# GasSensorModule_v2_1.net
KiCad netlist of a schematic drawn in EAGLE
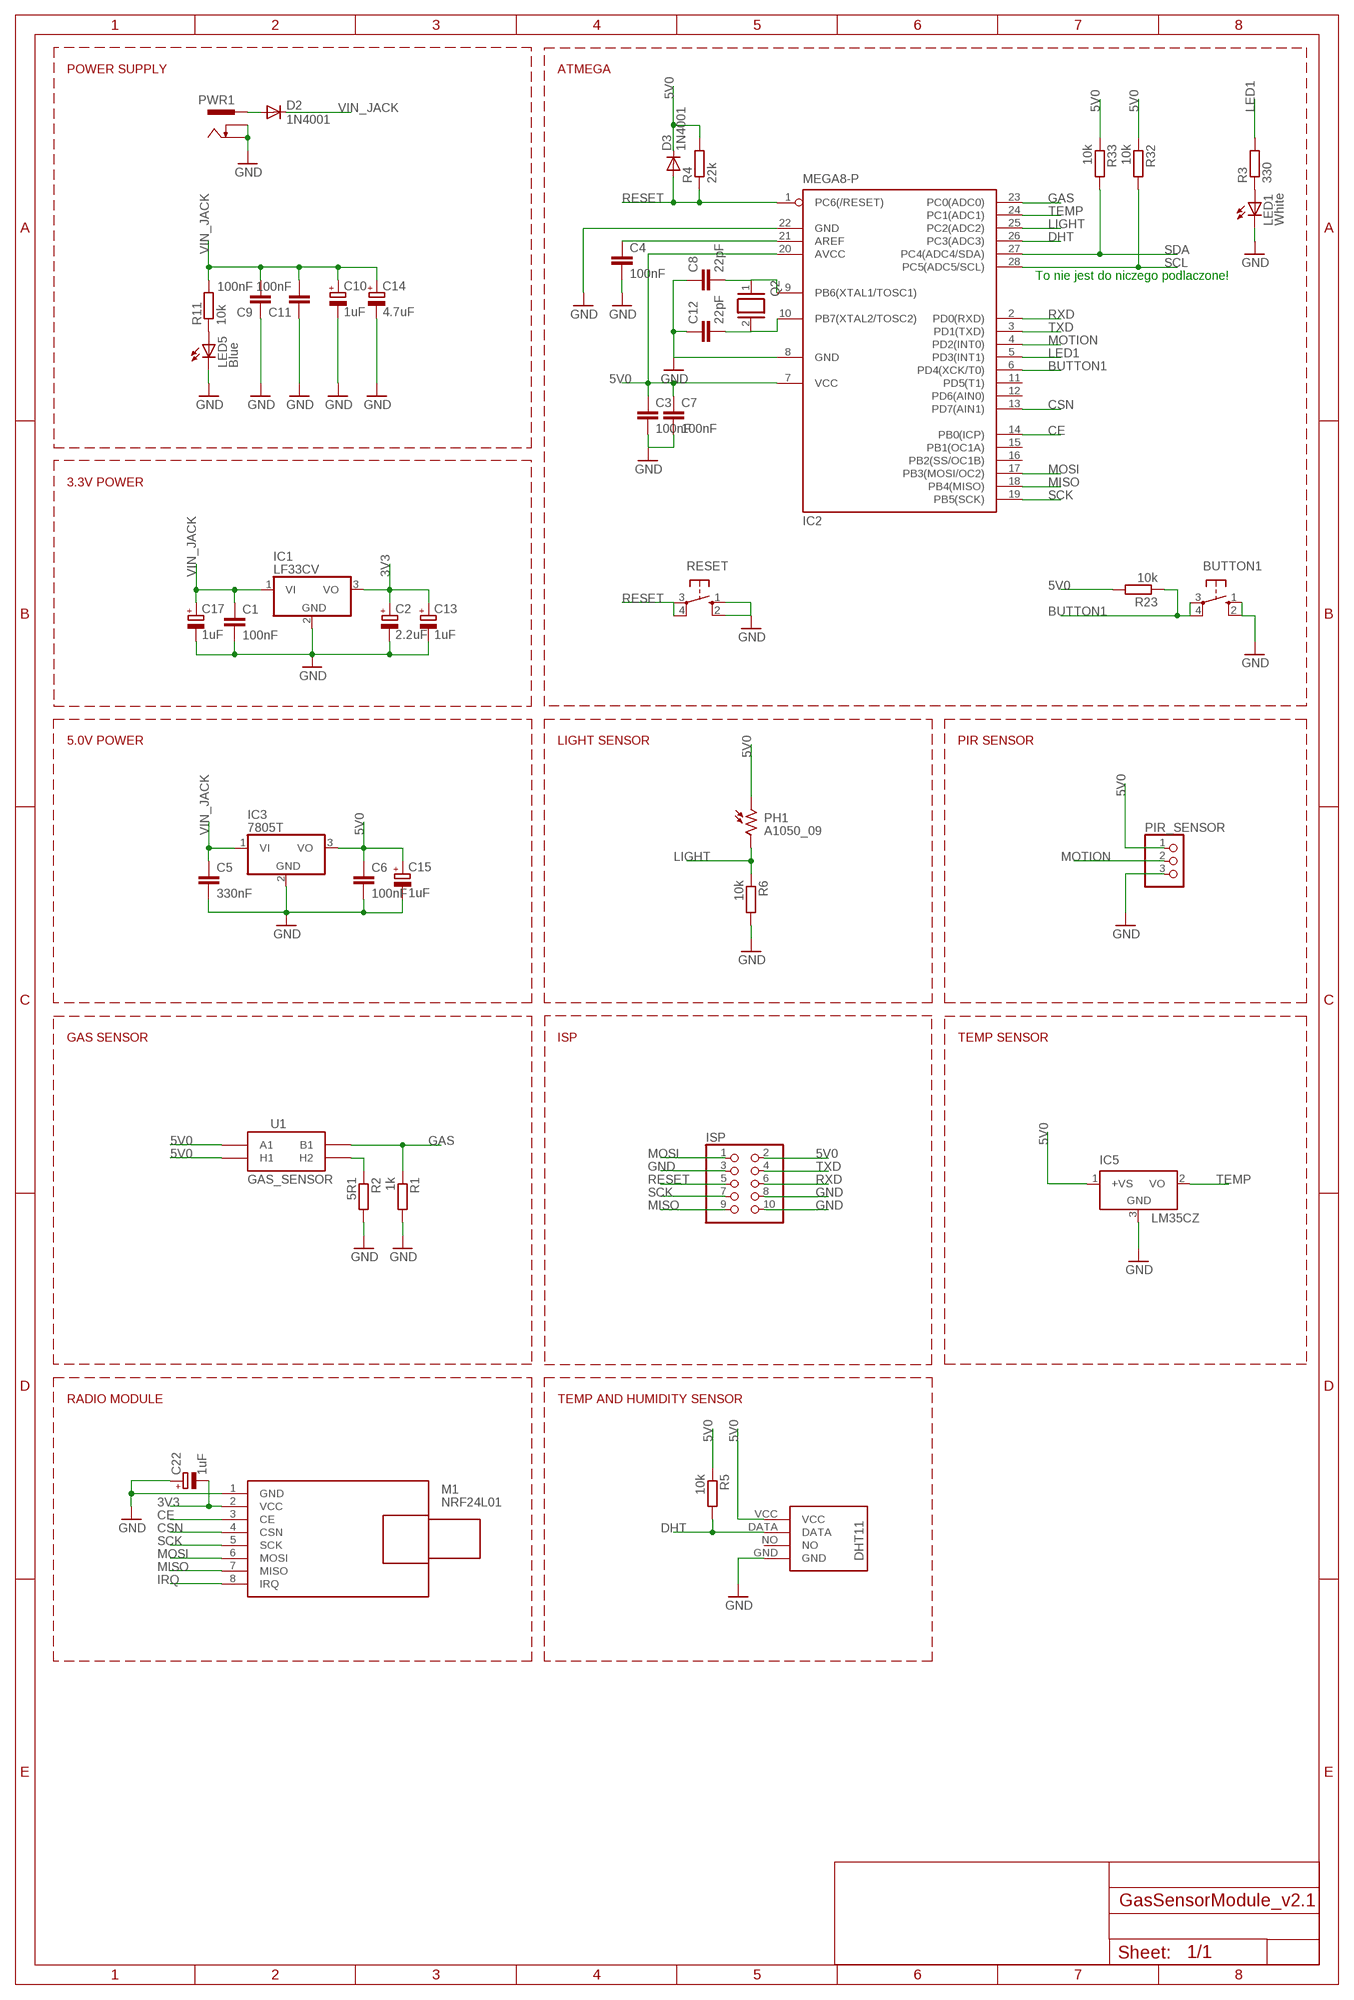
[diagram p0: schematic, sheet 1]

(export (version "E")
  (design (tool "Eeschema 10.0.6"))
  (components
    (comp (ref "BUTTON1")
      (value "10-XX")
      (footprint "eagle-import:B3F-10XX")
      (fields (field (name "MPN") "B3F-1000"))
      (libsource (lib "eagle-import") (part "10-XX"))
    )
    (comp (ref "C1")
      (value "100nF")
      (footprint "eagle-import:C025-025X050")
      (libsource (lib "eagle-import") (part "C-EU025-025X050"))
    )
    (comp (ref "C2")
      (value "2.2uF")
      (footprint "eagle-import:E2,5-5")
      (libsource (lib "eagle-import") (part "CPOL-EUE2.5-5"))
    )
    (comp (ref "C3")
      (value "100nF")
      (footprint "eagle-import:C025-025X050")
      (libsource (lib "eagle-import") (part "C-EU025-025X050"))
    )
    (comp (ref "C4")
      (value "100nF")
      (footprint "eagle-import:C025-025X050")
      (libsource (lib "eagle-import") (part "C-EU025-025X050"))
    )
    (comp (ref "C5")
      (value "330nF")
      (footprint "eagle-import:C025-025X050")
      (libsource (lib "eagle-import") (part "C-EU025-025X050"))
    )
    (comp (ref "C6")
      (value "100nF")
      (footprint "eagle-import:C025-025X050")
      (libsource (lib "eagle-import") (part "C-EU025-025X050"))
    )
    (comp (ref "C7")
      (value "100nF")
      (footprint "eagle-import:C025-025X050")
      (libsource (lib "eagle-import") (part "C-EU025-025X050"))
    )
    (comp (ref "C8")
      (value "22pF")
      (footprint "eagle-import:C025-025X050")
      (libsource (lib "eagle-import") (part "C-EU025-025X050"))
    )
    (comp (ref "C9")
      (value "100nF")
      (footprint "eagle-import:C025-025X050")
      (libsource (lib "eagle-import") (part "C-EU025-025X050"))
    )
    (comp (ref "C10")
      (value "1uF")
      (footprint "eagle-import:E2,5-5")
      (libsource (lib "eagle-import") (part "CPOL-EUE2.5-5"))
    )
    (comp (ref "C11")
      (value "100nF")
      (footprint "eagle-import:C025-025X050")
      (libsource (lib "eagle-import") (part "C-EU025-025X050"))
    )
    (comp (ref "C12")
      (value "22pF")
      (footprint "eagle-import:C025-025X050")
      (libsource (lib "eagle-import") (part "C-EU025-025X050"))
    )
    (comp (ref "C13")
      (value "1uF")
      (footprint "eagle-import:E2,5-5")
      (libsource (lib "eagle-import") (part "CPOL-EUE2.5-5"))
    )
    (comp (ref "C14")
      (value "4.7uF")
      (footprint "eagle-import:E2,5-5")
      (libsource (lib "eagle-import") (part "CPOL-EUE2.5-5"))
    )
    (comp (ref "C15")
      (value "1uF")
      (footprint "eagle-import:E2,5-5")
      (libsource (lib "eagle-import") (part "CPOL-EUE2.5-5"))
    )
    (comp (ref "C17")
      (value "1uF")
      (footprint "eagle-import:E2,5-5")
      (libsource (lib "eagle-import") (part "CPOL-EUE2.5-5"))
    )
    (comp (ref "C22")
      (value "1uF")
      (footprint "eagle-import:E2,5-5")
      (libsource (lib "eagle-import") (part "CPOL-EUE2.5-5"))
    )
    (comp (ref "D2")
      (value "1N4001")
      (footprint "eagle-import:DO41-10")
      (libsource (lib "eagle-import") (part "1N4004"))
    )
    (comp (ref "D3")
      (value "1N4001")
      (footprint "eagle-import:DO41-10")
      (libsource (lib "eagle-import") (part "1N4004"))
    )
    (comp (ref "IC1")
      (value "LF33CV")
      (footprint "eagle-import:TO220H")
      (libsource (lib "eagle-import") (part "78T05"))
    )
    (comp (ref "IC2")
      (value "MEGA8-P")
      (footprint "eagle-import:DIL28-3")
      (libsource (lib "eagle-import") (part "MEGA8-P"))
    )
    (comp (ref "IC3")
      (value "7805T")
      (footprint "eagle-import:TO220H")
      (libsource (lib "eagle-import") (part "78T05"))
    )
    (comp (ref "IC5")
      (value "LM35CZ")
      (footprint "eagle-import:TO92")
      (libsource (lib "eagle-import") (part "LM35CZ"))
    )
    (comp (ref "ISP")
      (value "PINHD-2X5")
      (footprint "eagle-import:2X05")
      (libsource (lib "eagle-import") (part "PINHD-2X5"))
    )
    (comp (ref "LED1")
      (value "White")
      (footprint "eagle-import:LED3MM")
      (libsource (lib "eagle-import") (part "LED3MM"))
    )
    (comp (ref "LED5")
      (value "Blue")
      (footprint "eagle-import:LED3MM")
      (libsource (lib "eagle-import") (part "LED3MM"))
    )
    (comp (ref "M1")
      (value "NRF24L01")
      (footprint "eagle-import:WIRELESS-NRD24L01-PA-EXT")
      (libsource (lib "eagle-import") (part "WIRELESS-NRF24L01-PA-EXT"))
    )
    (comp (ref "PH1")
      (value "A1050_09")
      (footprint "eagle-import:T0-46-A10XX")
      (libsource (lib "eagle-import") (part "A1050_09"))
    )
    (comp (ref "PIR_SENSOR")
      (value "PINHD-1X3")
      (footprint "eagle-import:1X03")
      (libsource (lib "eagle-import") (part "PINHD-1X3"))
    )
    (comp (ref "PWR1")
      (value "PWR-JAKPWR_JACK_UNI_MILLING")
      (footprint "eagle-import:PWR_JACK_UNI_MILLING")
      (libsource (lib "eagle-import") (part "PWR-JAKPWR_JACK_UNI_MILLING"))
    )
    (comp (ref "Q2")
      (value "XTAL/S")
      (footprint "eagle-import:QS")
      (libsource (lib "eagle-import") (part "XTAL/S"))
    )
    (comp (ref "R1")
      (value "1k")
      (footprint "eagle-import:0207_10")
      (libsource (lib "eagle-import") (part "R-EU_0207/10"))
    )
    (comp (ref "R2")
      (value "5R1")
      (footprint "eagle-import:0207_10")
      (libsource (lib "eagle-import") (part "R-EU_0207/10"))
    )
    (comp (ref "R3")
      (value "330")
      (footprint "eagle-import:0207_10")
      (libsource (lib "eagle-import") (part "R-EU_0207/10"))
    )
    (comp (ref "R4")
      (value "22k")
      (footprint "eagle-import:0207_10")
      (libsource (lib "eagle-import") (part "R-EU_0207/10"))
    )
    (comp (ref "R5")
      (value "10k")
      (footprint "eagle-import:0207_10")
      (libsource (lib "eagle-import") (part "R-EU_0207/10"))
    )
    (comp (ref "R6")
      (value "10k")
      (footprint "eagle-import:0207_10")
      (libsource (lib "eagle-import") (part "R-EU_0207/10"))
    )
    (comp (ref "R11")
      (value "10k")
      (footprint "eagle-import:0207_10")
      (libsource (lib "eagle-import") (part "R-EU_0207/10"))
    )
    (comp (ref "R23")
      (value "10k")
      (footprint "eagle-import:0207_10")
      (libsource (lib "eagle-import") (part "R-EU_0207/10"))
    )
    (comp (ref "R32")
      (value "10k")
      (footprint "eagle-import:0207_10")
      (libsource (lib "eagle-import") (part "R-EU_0207/10"))
    )
    (comp (ref "R33")
      (value "10k")
      (footprint "eagle-import:0207_10")
      (libsource (lib "eagle-import") (part "R-EU_0207/10"))
    )
    (comp (ref "RESET")
      (value "10-XX")
      (footprint "eagle-import:B3F-10XX")
      (fields (field (name "MPN") "B3F-1000"))
      (libsource (lib "eagle-import") (part "10-XX"))
    )
    (comp (ref "U$1")
      (value "DHT11-PION.")
      (footprint "eagle-import:DHT11-PION.")
      (libsource (lib "eagle-import") (part "DHT11-PION."))
    )
    (comp (ref "U1")
      (value "GAS_SENSOR")
      (footprint "eagle-import:MQ-3")
      (libsource (lib "eagle-import") (part "GAS_SENSOR"))
    )
  )
  (nets
    (net (code "1") (name "/3V3") (class "Default")
      (node (ref "C13") (pin "+") (pinfunction "+_+") (pintype "passive"))
      (node (ref "C2") (pin "+") (pinfunction "+_+") (pintype "passive"))
      (node (ref "C22") (pin "-") (pinfunction "-_-") (pintype "passive"))
      (node (ref "IC1") (pin "3") (pinfunction "VO_3") (pintype "passive"))
      (node (ref "M1") (pin "2") (pinfunction "VCC_2") (pintype "power_in"))
    )
    (net (code "2") (name "/5V0") (class "Default")
      (node (ref "C15") (pin "+") (pinfunction "+_+") (pintype "passive"))
      (node (ref "C3") (pin "1") (pinfunction "1_1") (pintype "passive"))
      (node (ref "C6") (pin "1") (pinfunction "1_1") (pintype "passive"))
      (node (ref "C7") (pin "1") (pinfunction "1_1") (pintype "passive"))
      (node (ref "D3") (pin "C") (pinfunction "C_C") (pintype "passive"))
      (node (ref "IC2") (pin "20") (pinfunction "AVCC_20") (pintype "power_in"))
      (node (ref "IC2") (pin "7") (pinfunction "VCC_7") (pintype "power_in"))
      (node (ref "IC3") (pin "3") (pinfunction "VO_3") (pintype "passive"))
      (node (ref "IC5") (pin "1") (pinfunction "+VS_1") (pintype "input"))
      (node (ref "ISP") (pin "2") (pinfunction "2_2") (pintype "passive"))
      (node (ref "PH1") (pin "1") (pinfunction "1_1") (pintype "passive"))
      (node (ref "PIR_SENSOR") (pin "1") (pinfunction "1_1") (pintype "passive"))
      (node (ref "R23") (pin "2") (pinfunction "2_2") (pintype "passive"))
      (node (ref "R32") (pin "1") (pinfunction "1_1") (pintype "passive"))
      (node (ref "R33") (pin "1") (pinfunction "1_1") (pintype "passive"))
      (node (ref "R4") (pin "2") (pinfunction "2_2") (pintype "passive"))
      (node (ref "R5") (pin "1") (pinfunction "1_1") (pintype "passive"))
      (node (ref "U$1") (pin "VCC") (pinfunction "VCC_VCC") (pintype "bidirectional"))
      (node (ref "U1") (pin "A1") (pinfunction "A1_A1") (pintype "bidirectional"))
      (node (ref "U1") (pin "HA") (pinfunction "H1_HA") (pintype "bidirectional"))
    )
    (net (code "3") (name "/BUTTON1") (class "Default")
      (node (ref "BUTTON1") (pin "3") (pinfunction "P_3") (pintype "passive"))
      (node (ref "BUTTON1") (pin "4") (pinfunction "P1_4") (pintype "passive"))
      (node (ref "IC2") (pin "6") (pinfunction "PD4(XCK/T0)_6") (pintype "bidirectional"))
      (node (ref "R23") (pin "1") (pinfunction "1_1") (pintype "passive"))
    )
    (net (code "4") (name "/CE") (class "Default")
      (node (ref "IC2") (pin "14") (pinfunction "PB0(ICP)_14") (pintype "bidirectional"))
      (node (ref "M1") (pin "3") (pinfunction "CE_3") (pintype "bidirectional"))
    )
    (net (code "5") (name "/CSN") (class "Default")
      (node (ref "IC2") (pin "13") (pinfunction "PD7(AIN1)_13") (pintype "bidirectional"))
      (node (ref "M1") (pin "4") (pinfunction "CSN_4") (pintype "bidirectional"))
    )
    (net (code "6") (name "/DHT") (class "Default")
      (node (ref "IC2") (pin "26") (pinfunction "PC3(ADC3)_26") (pintype "bidirectional"))
      (node (ref "R5") (pin "2") (pinfunction "2_2") (pintype "passive"))
      (node (ref "U$1") (pin "DATA") (pinfunction "DATA_DATA") (pintype "bidirectional"))
    )
    (net (code "7") (name "/GAS") (class "Default")
      (node (ref "IC2") (pin "23") (pinfunction "PC0(ADC0)_23") (pintype "bidirectional"))
      (node (ref "R1") (pin "1") (pinfunction "1_1") (pintype "passive"))
      (node (ref "U1") (pin "B1") (pinfunction "B1_B1") (pintype "bidirectional"))
    )
    (net (code "8") (name "/IRQ") (class "Default")
      (node (ref "M1") (pin "8") (pinfunction "IRQ_8") (pintype "bidirectional"))
    )
    (net (code "9") (name "/LED1") (class "Default")
      (node (ref "IC2") (pin "5") (pinfunction "PD3(INT1)_5") (pintype "bidirectional"))
      (node (ref "R3") (pin "2") (pinfunction "2_2") (pintype "passive"))
    )
    (net (code "10") (name "/LIGHT") (class "Default")
      (node (ref "IC2") (pin "25") (pinfunction "PC2(ADC2)_25") (pintype "bidirectional"))
      (node (ref "PH1") (pin "2") (pinfunction "2_2") (pintype "passive"))
      (node (ref "R6") (pin "1") (pinfunction "1_1") (pintype "passive"))
    )
    (net (code "11") (name "/MISO") (class "Default")
      (node (ref "IC2") (pin "18") (pinfunction "PB4(MISO)_18") (pintype "bidirectional"))
      (node (ref "ISP") (pin "9") (pinfunction "9_9") (pintype "passive"))
      (node (ref "M1") (pin "7") (pinfunction "MISO_7") (pintype "bidirectional"))
    )
    (net (code "12") (name "/MOSI") (class "Default")
      (node (ref "IC2") (pin "17") (pinfunction "PB3(MOSI/OC2)_17") (pintype "bidirectional"))
      (node (ref "ISP") (pin "1") (pinfunction "1_1") (pintype "passive"))
      (node (ref "M1") (pin "6") (pinfunction "MOSI_6") (pintype "bidirectional"))
    )
    (net (code "13") (name "/MOTION") (class "Default")
      (node (ref "IC2") (pin "4") (pinfunction "PD2(INT0)_4") (pintype "bidirectional"))
      (node (ref "PIR_SENSOR") (pin "2") (pinfunction "2_2") (pintype "passive"))
    )
    (net (code "14") (name "/RESET") (class "Default")
      (node (ref "D3") (pin "A") (pinfunction "A_A") (pintype "passive"))
      (node (ref "IC2") (pin "1") (pinfunction "PC6(/RESET)_1") (pintype "bidirectional"))
      (node (ref "ISP") (pin "5") (pinfunction "5_5") (pintype "passive"))
      (node (ref "R4") (pin "1") (pinfunction "1_1") (pintype "passive"))
      (node (ref "RESET") (pin "3") (pinfunction "P_3") (pintype "passive"))
      (node (ref "RESET") (pin "4") (pinfunction "P1_4") (pintype "passive"))
    )
    (net (code "15") (name "/RXD") (class "Default")
      (node (ref "IC2") (pin "2") (pinfunction "PD0(RXD)_2") (pintype "bidirectional"))
      (node (ref "ISP") (pin "6") (pinfunction "6_6") (pintype "passive"))
    )
    (net (code "16") (name "/SCK") (class "Default")
      (node (ref "IC2") (pin "19") (pinfunction "PB5(SCK)_19") (pintype "bidirectional"))
      (node (ref "ISP") (pin "7") (pinfunction "7_7") (pintype "passive"))
      (node (ref "M1") (pin "5") (pinfunction "SCK_5") (pintype "bidirectional"))
    )
    (net (code "17") (name "/SCL") (class "Default")
      (node (ref "IC2") (pin "28") (pinfunction "PC5(ADC5/SCL)_28") (pintype "bidirectional"))
      (node (ref "R32") (pin "2") (pinfunction "2_2") (pintype "passive"))
    )
    (net (code "18") (name "/SDA") (class "Default")
      (node (ref "IC2") (pin "27") (pinfunction "PC4(ADC4/SDA)_27") (pintype "bidirectional"))
      (node (ref "R33") (pin "2") (pinfunction "2_2") (pintype "passive"))
    )
    (net (code "19") (name "/TEMP") (class "Default")
      (node (ref "IC2") (pin "24") (pinfunction "PC1(ADC1)_24") (pintype "bidirectional"))
      (node (ref "IC5") (pin "2") (pinfunction "VO_2") (pintype "input"))
    )
    (net (code "20") (name "/TXD") (class "Default")
      (node (ref "IC2") (pin "3") (pinfunction "PD1(TXD)_3") (pintype "bidirectional"))
      (node (ref "ISP") (pin "4") (pinfunction "4_4") (pintype "passive"))
    )
    (net (code "21") (name "/VIN_JACK") (class "Default")
      (node (ref "C1") (pin "1") (pinfunction "1_1") (pintype "passive"))
      (node (ref "C10") (pin "+") (pinfunction "+_+") (pintype "passive"))
      (node (ref "C11") (pin "2") (pinfunction "2_2") (pintype "passive"))
      (node (ref "C14") (pin "+") (pinfunction "+_+") (pintype "passive"))
      (node (ref "C17") (pin "+") (pinfunction "+_+") (pintype "passive"))
      (node (ref "C5") (pin "1") (pinfunction "1_1") (pintype "passive"))
      (node (ref "C9") (pin "2") (pinfunction "2_2") (pintype "passive"))
      (node (ref "D2") (pin "C") (pinfunction "C_C") (pintype "passive"))
      (node (ref "IC1") (pin "1") (pinfunction "VI_1") (pintype "input"))
      (node (ref "IC3") (pin "1") (pinfunction "VI_1") (pintype "input"))
      (node (ref "R11") (pin "2") (pinfunction "2_2") (pintype "passive"))
    )
    (net (code "22") (name "GND") (class "Default")
      (node (ref "BUTTON1") (pin "1") (pinfunction "S_1") (pintype "passive"))
      (node (ref "BUTTON1") (pin "2") (pinfunction "S1_2") (pintype "passive"))
      (node (ref "C1") (pin "2") (pinfunction "2_2") (pintype "passive"))
      (node (ref "C10") (pin "-") (pinfunction "-_-") (pintype "passive"))
      (node (ref "C11") (pin "1") (pinfunction "1_1") (pintype "passive"))
      (node (ref "C12") (pin "1") (pinfunction "1_1") (pintype "passive"))
      (node (ref "C13") (pin "-") (pinfunction "-_-") (pintype "passive"))
      (node (ref "C14") (pin "-") (pinfunction "-_-") (pintype "passive"))
      (node (ref "C15") (pin "-") (pinfunction "-_-") (pintype "passive"))
      (node (ref "C17") (pin "-") (pinfunction "-_-") (pintype "passive"))
      (node (ref "C2") (pin "-") (pinfunction "-_-") (pintype "passive"))
      (node (ref "C22") (pin "+") (pinfunction "+_+") (pintype "passive"))
      (node (ref "C3") (pin "2") (pinfunction "2_2") (pintype "passive"))
      (node (ref "C4") (pin "2") (pinfunction "2_2") (pintype "passive"))
      (node (ref "C5") (pin "2") (pinfunction "2_2") (pintype "passive"))
      (node (ref "C6") (pin "2") (pinfunction "2_2") (pintype "passive"))
      (node (ref "C7") (pin "2") (pinfunction "2_2") (pintype "passive"))
      (node (ref "C8") (pin "1") (pinfunction "1_1") (pintype "passive"))
      (node (ref "C9") (pin "1") (pinfunction "1_1") (pintype "passive"))
      (node (ref "IC1") (pin "2") (pinfunction "GND_2") (pintype "passive"))
      (node (ref "IC2") (pin "22") (pinfunction "GND_22") (pintype "power_in"))
      (node (ref "IC2") (pin "8") (pinfunction "GND_8") (pintype "power_in"))
      (node (ref "IC3") (pin "2") (pinfunction "GND_2") (pintype "passive"))
      (node (ref "IC5") (pin "3") (pinfunction "GND_3") (pintype "power_in"))
      (node (ref "ISP") (pin "10") (pinfunction "10_10") (pintype "passive"))
      (node (ref "ISP") (pin "3") (pinfunction "3_3") (pintype "passive"))
      (node (ref "ISP") (pin "8") (pinfunction "8_8") (pintype "passive"))
      (node (ref "LED1") (pin "K") (pinfunction "C_K") (pintype "passive"))
      (node (ref "LED5") (pin "K") (pinfunction "C_K") (pintype "passive"))
      (node (ref "M1") (pin "1") (pinfunction "GND_1") (pintype "power_in"))
      (node (ref "PIR_SENSOR") (pin "3") (pinfunction "3_3") (pintype "passive"))
      (node (ref "PWR1") (pin "-") (pinfunction "-_-") (pintype "passive"))
      (node (ref "PWR1") (pin "--") (pinfunction "--_--") (pintype "passive"))
      (node (ref "R1") (pin "2") (pinfunction "2_2") (pintype "passive"))
      (node (ref "R2") (pin "2") (pinfunction "2_2") (pintype "passive"))
      (node (ref "R6") (pin "2") (pinfunction "2_2") (pintype "passive"))
      (node (ref "RESET") (pin "1") (pinfunction "S_1") (pintype "passive"))
      (node (ref "RESET") (pin "2") (pinfunction "S1_2") (pintype "passive"))
      (node (ref "U$1") (pin "GND") (pinfunction "GND_GND") (pintype "bidirectional"))
    )
    (net (code "23") (name "Net-(D2-PadA)") (class "Default")
      (node (ref "D2") (pin "A") (pinfunction "A_A") (pintype "passive"))
      (node (ref "PWR1") (pin "+") (pinfunction "+_+") (pintype "passive"))
    )
    (net (code "24") (name "Net-(IC2-AREF)") (class "Default")
      (node (ref "C4") (pin "1") (pinfunction "1_1") (pintype "passive"))
      (node (ref "IC2") (pin "21") (pinfunction "AREF_21") (pintype "passive"))
    )
    (net (code "25") (name "Net-(IC2-PB6(XTAL1{slash}TOSC1))") (class "Default")
      (node (ref "C8") (pin "2") (pinfunction "2_2") (pintype "passive"))
      (node (ref "IC2") (pin "9") (pinfunction "PB6(XTAL1/TOSC1)_9") (pintype "bidirectional"))
      (node (ref "Q2") (pin "1") (pinfunction "1_1") (pintype "passive"))
    )
    (net (code "26") (name "Net-(IC2-PB7(XTAL2{slash}TOSC2))") (class "Default")
      (node (ref "C12") (pin "2") (pinfunction "2_2") (pintype "passive"))
      (node (ref "IC2") (pin "10") (pinfunction "PB7(XTAL2/TOSC2)_10") (pintype "bidirectional"))
      (node (ref "Q2") (pin "2") (pinfunction "2_2") (pintype "passive"))
    )
    (net (code "27") (name "Net-(LED1-PadA)") (class "Default")
      (node (ref "LED1") (pin "A") (pinfunction "A_A") (pintype "passive"))
      (node (ref "R3") (pin "1") (pinfunction "1_1") (pintype "passive"))
    )
    (net (code "28") (name "Net-(LED5-PadA)") (class "Default")
      (node (ref "LED5") (pin "A") (pinfunction "A_A") (pintype "passive"))
      (node (ref "R11") (pin "1") (pinfunction "1_1") (pintype "passive"))
    )
    (net (code "29") (name "Net-(U1-H2)") (class "Default")
      (node (ref "R2") (pin "1") (pinfunction "1_1") (pintype "passive"))
      (node (ref "U1") (pin "HB") (pinfunction "H2_HB") (pintype "bidirectional"))
    )
    (net (code "30") (name "unconnected-(IC2-PB1(OC1A)-Pad15)") (class "Default")
      (node (ref "IC2") (pin "15") (pinfunction "PB1(OC1A)_15") (pintype "bidirectional"))
    )
    (net (code "31") (name "unconnected-(IC2-PB2(SS{slash}OC1B)-Pad16)") (class "Default")
      (node (ref "IC2") (pin "16") (pinfunction "PB2(SS/OC1B)_16") (pintype "bidirectional"))
    )
    (net (code "32") (name "unconnected-(IC2-PD5(T1)-Pad11)") (class "Default")
      (node (ref "IC2") (pin "11") (pinfunction "PD5(T1)_11") (pintype "bidirectional"))
    )
    (net (code "33") (name "unconnected-(IC2-PD6(AIN0)-Pad12)") (class "Default")
      (node (ref "IC2") (pin "12") (pinfunction "PD6(AIN0)_12") (pintype "bidirectional"))
    )
    (net (code "34") (name "unconnected-(U$1-PadNO)") (class "Default")
      (node (ref "U$1") (pin "NO") (pinfunction "NO_NO") (pintype "bidirectional"))
    )
  )
)
